# SensorStation_Board_v0_6.net
KiCad netlist of a schematic drawn in EAGLE
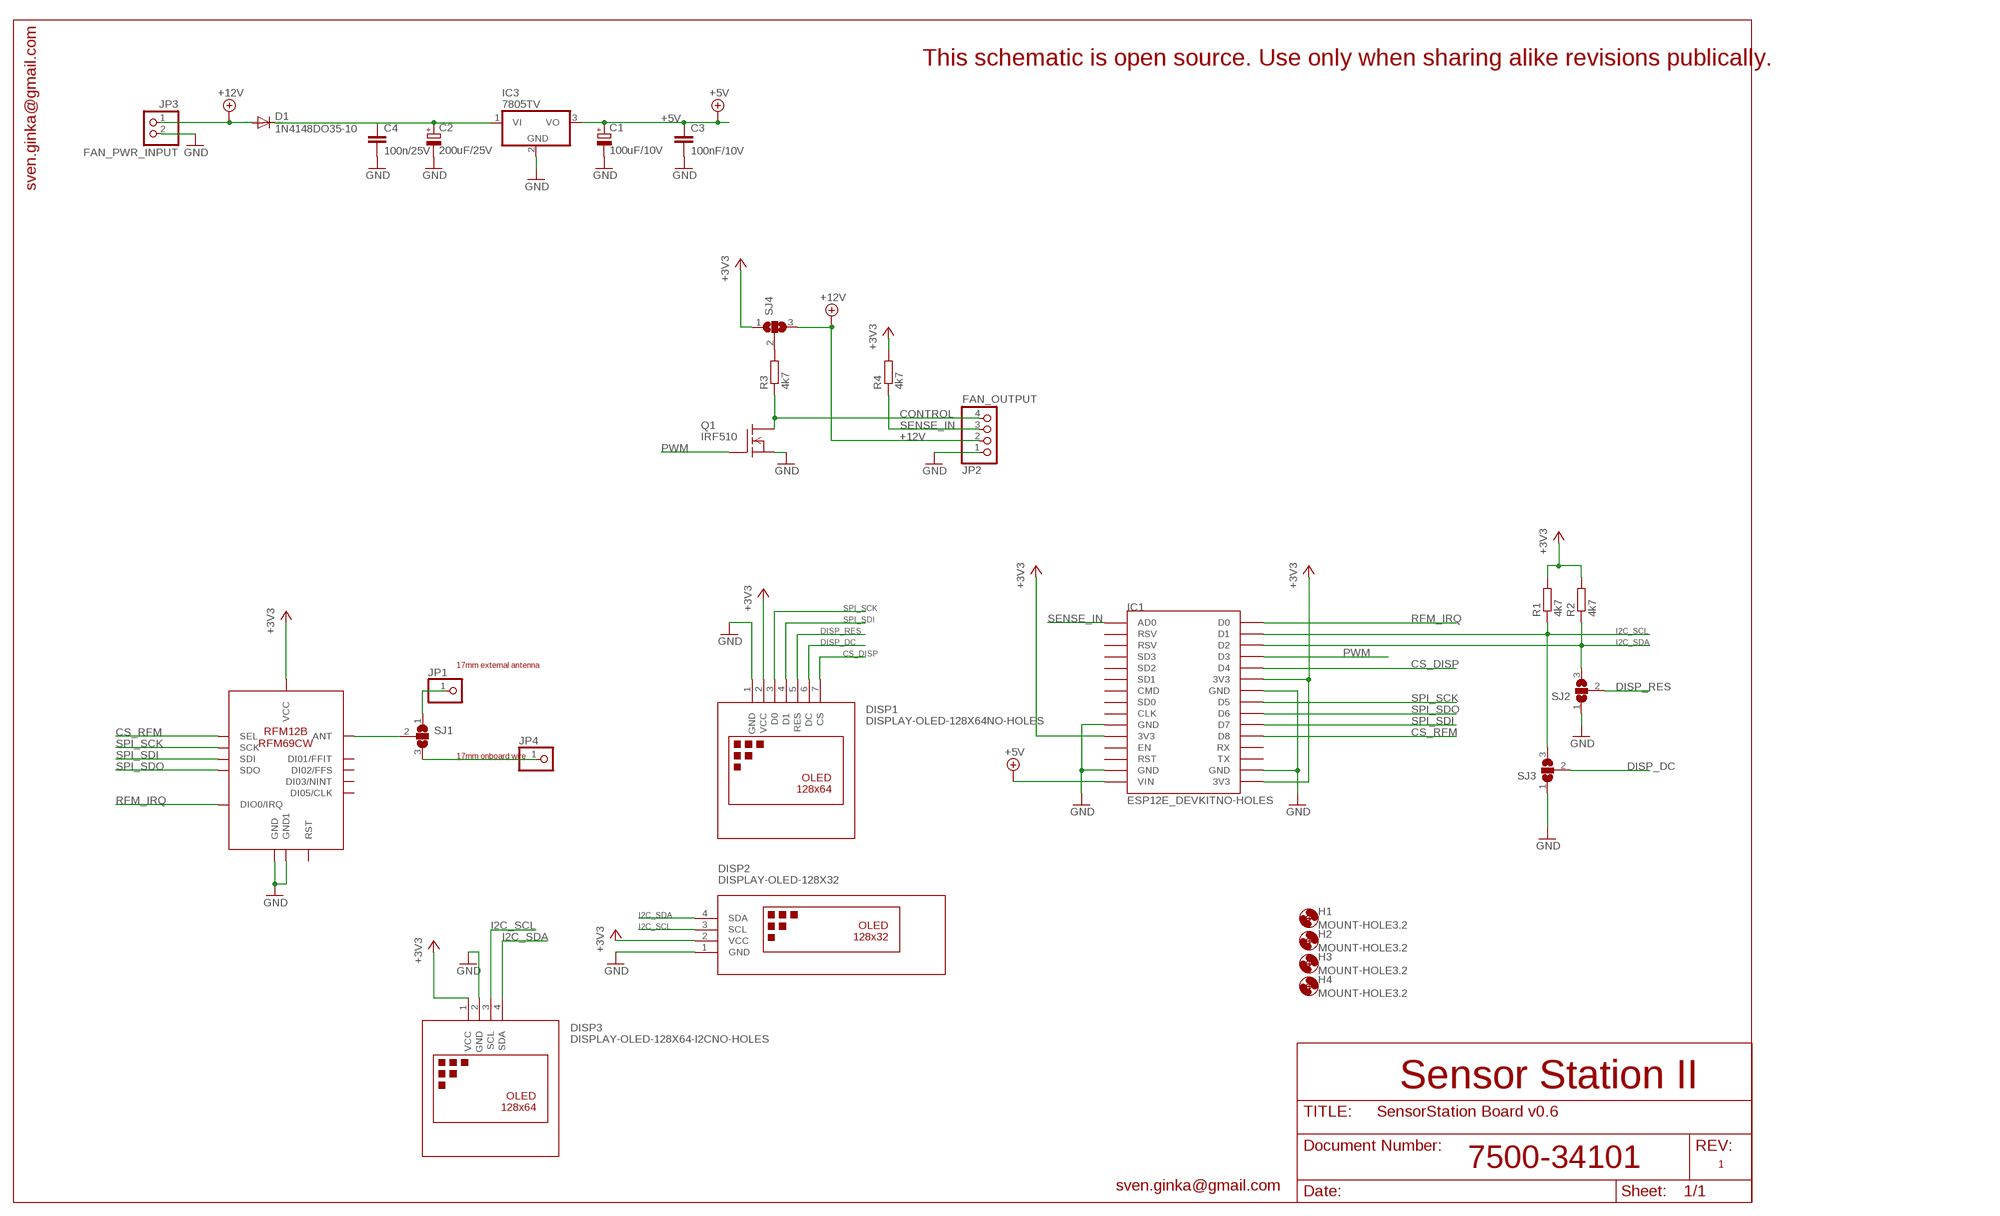
[diagram p0: schematic, sheet 1]

(export (version "E")
  (design (tool "Eeschema 10.0.6"))
  (components
    (comp (ref "C1")
      (value "100uF/10V")
      (footprint "eagle-import:E2,5-6")
      (libsource (lib "eagle-import") (part "CPOL-EUE2.5-6"))
    )
    (comp (ref "C2")
      (value "200uF/25V")
      (footprint "eagle-import:E2,5-6")
      (libsource (lib "eagle-import") (part "CPOL-EUE2.5-6"))
    )
    (comp (ref "C3")
      (value "100nF/10V")
      (footprint "eagle-import:C025-025X050")
      (libsource (lib "eagle-import") (part "C-EU025-025X050"))
    )
    (comp (ref "C4")
      (value "100n/25V")
      (footprint "eagle-import:C025-025X050")
      (libsource (lib "eagle-import") (part "C-EU025-025X050"))
    )
    (comp (ref "D1")
      (value "1N4148DO35-10")
      (footprint "eagle-import:DO35-10")
      (libsource (lib "eagle-import") (part "1N4148DO35-10"))
    )
    (comp (ref "DISP1")
      (value "DISPLAY-OLED-128X64NO-HOLES")
      (footprint "eagle-import:DISPLAY-OLED-128X64-NO-HOLES")
      (libsource (lib "eagle-import") (part "DISPLAY-OLED-128X64NO-HOLES"))
    )
    (comp (ref "DISP2")
      (value "DISPLAY-OLED-128X32")
      (footprint "eagle-import:DISPLAY-OLED-128X32")
      (libsource (lib "eagle-import") (part "DISPLAY-OLED-128X32"))
    )
    (comp (ref "DISP3")
      (value "DISPLAY-OLED-128X64-I2CNO-HOLES")
      (footprint "eagle-import:DISPLAY-OLED-128X64-I2C-NO-HOLES")
      (libsource (lib "eagle-import") (part "DISPLAY-OLED-128X64-I2CNO-HOLES"))
    )
    (comp (ref "H1")
      (value "MOUNT-HOLE3.2")
      (footprint "eagle-import:3,2")
      (libsource (lib "eagle-import") (part "MOUNT-HOLE3.2"))
    )
    (comp (ref "H2")
      (value "MOUNT-HOLE3.2")
      (footprint "eagle-import:3,2")
      (libsource (lib "eagle-import") (part "MOUNT-HOLE3.2"))
    )
    (comp (ref "H3")
      (value "MOUNT-HOLE3.2")
      (footprint "eagle-import:3,2")
      (libsource (lib "eagle-import") (part "MOUNT-HOLE3.2"))
    )
    (comp (ref "H4")
      (value "MOUNT-HOLE3.2")
      (footprint "eagle-import:3,2")
      (libsource (lib "eagle-import") (part "MOUNT-HOLE3.2"))
    )
    (comp (ref "IC1")
      (value "ESP12E_DEVKITNO-HOLES")
      (footprint "eagle-import:ESP12E_DEVKIT-NO-HOLES")
      (libsource (lib "eagle-import") (part "ESP12E_DEVKITNO-HOLES"))
    )
    (comp (ref "IC2")
      (value "RFM12B/69CW")
      (footprint "eagle-import:RFM12B_69CW")
      (libsource (lib "eagle-import") (part "RFM12B/69CW"))
    )
    (comp (ref "IC3")
      (value "7805TV")
      (footprint "eagle-import:TO220V")
      (libsource (lib "eagle-import") (part "78TV05"))
    )
    (comp (ref "JP1")
      (value "PINHD-1X1")
      (footprint "eagle-import:1X01")
      (libsource (lib "eagle-import") (part "PINHD-1X1"))
    )
    (comp (ref "JP2")
      (value "FAN_OUTPUT")
      (footprint "eagle-import:1X04")
      (libsource (lib "eagle-import") (part "PINHD-1X4"))
    )
    (comp (ref "JP3")
      (value "FAN_PWR_INPUT")
      (footprint "eagle-import:1X02")
      (libsource (lib "eagle-import") (part "PINHD-1X2"))
    )
    (comp (ref "JP4")
      (value "PINHD-1X1")
      (footprint "eagle-import:1X01")
      (libsource (lib "eagle-import") (part "PINHD-1X1"))
    )
    (comp (ref "Q1")
      (value "IRF510")
      (footprint "eagle-import:TO220")
      (libsource (lib "eagle-import") (part "IRF510"))
    )
    (comp (ref "R1")
      (value "4k7")
      (footprint "eagle-import:0204_5")
      (libsource (lib "eagle-import") (part "R-EU_0204/5"))
    )
    (comp (ref "R2")
      (value "4k7")
      (footprint "eagle-import:0204_5")
      (libsource (lib "eagle-import") (part "R-EU_0204/5"))
    )
    (comp (ref "R3")
      (value "4k7")
      (footprint "eagle-import:0204_5")
      (libsource (lib "eagle-import") (part "R-EU_0204/5"))
    )
    (comp (ref "R4")
      (value "4k7")
      (footprint "eagle-import:0204_5")
      (libsource (lib "eagle-import") (part "R-EU_0204/5"))
    )
    (comp (ref "SJ1")
      (value "SJ2W")
      (footprint "eagle-import:SJ_2")
      (libsource (lib "eagle-import") (part "SJ2W"))
    )
    (comp (ref "SJ2")
      (value "SJ2W")
      (footprint "eagle-import:SJ_2")
      (libsource (lib "eagle-import") (part "SJ2W"))
    )
    (comp (ref "SJ3")
      (value "SJ2W")
      (footprint "eagle-import:SJ_2")
      (libsource (lib "eagle-import") (part "SJ2W"))
    )
    (comp (ref "SJ4")
      (value "SJ2W")
      (footprint "eagle-import:SJ_2")
      (libsource (lib "eagle-import") (part "SJ2W"))
    )
  )
  (nets
    (net (code "1") (name "+3V3") (class "Default")
      (node (ref "DISP1") (pin "2") (pinfunction "VCC_2") (pintype "power_in"))
      (node (ref "DISP2") (pin "2") (pinfunction "VCC_2") (pintype "power_in"))
      (node (ref "DISP3") (pin "1") (pinfunction "VCC_1") (pintype "power_in"))
      (node (ref "IC1") (pin "3V3@0") (pinfunction "3V3_3V3@0") (pintype "bidirectional"))
      (node (ref "IC1") (pin "3V3@1") (pinfunction "3V3_3V3@1") (pintype "bidirectional"))
      (node (ref "IC1") (pin "3V3@2") (pinfunction "3V3_3V3@2") (pintype "bidirectional"))
      (node (ref "IC2") (pin "VDD") (pinfunction "VCC_VDD") (pintype "power_in"))
      (node (ref "R1") (pin "2") (pinfunction "2_2") (pintype "passive"))
      (node (ref "R2") (pin "2") (pinfunction "2_2") (pintype "passive"))
      (node (ref "R4") (pin "2") (pinfunction "2_2") (pintype "passive"))
      (node (ref "SJ4") (pin "1") (pinfunction "1_1") (pintype "passive"))
    )
    (net (code "2") (name "+5V") (class "Default")
      (node (ref "C1") (pin "+") (pinfunction "+_+") (pintype "passive"))
      (node (ref "C3") (pin "1") (pinfunction "1_1") (pintype "passive"))
      (node (ref "IC1") (pin "VIN") (pinfunction "VIN_VIN") (pintype "bidirectional"))
      (node (ref "IC3") (pin "3") (pinfunction "VO_3") (pintype "passive"))
    )
    (net (code "3") (name "+12V") (class "Default")
      (node (ref "D1") (pin "A") (pinfunction "A_A") (pintype "passive"))
      (node (ref "JP2") (pin "2") (pinfunction "2_2") (pintype "passive"))
      (node (ref "JP3") (pin "1") (pinfunction "1_1") (pintype "passive"))
      (node (ref "SJ4") (pin "3") (pinfunction "3_3") (pintype "passive"))
    )
    (net (code "4") (name "/CONTROL") (class "Default")
      (node (ref "JP2") (pin "4") (pinfunction "4_4") (pintype "passive"))
      (node (ref "Q1") (pin "2") (pinfunction "D_2") (pintype "passive"))
      (node (ref "R3") (pin "1") (pinfunction "1_1") (pintype "passive"))
    )
    (net (code "5") (name "/CS_DISP") (class "Default")
      (node (ref "DISP1") (pin "7") (pinfunction "CS_7") (pintype "bidirectional"))
      (node (ref "IC1") (pin "D4") (pinfunction "D4_D4") (pintype "bidirectional"))
    )
    (net (code "6") (name "/CS_RFM") (class "Default")
      (node (ref "IC1") (pin "D8") (pinfunction "D8_D8") (pintype "bidirectional"))
      (node (ref "IC2") (pin "SEL") (pinfunction "SEL_SEL") (pintype "input"))
    )
    (net (code "7") (name "/DISP_DC") (class "Default")
      (node (ref "DISP1") (pin "6") (pinfunction "DC_6") (pintype "bidirectional"))
      (node (ref "SJ3") (pin "2") (pinfunction "2_2") (pintype "passive"))
    )
    (net (code "8") (name "/DISP_RES") (class "Default")
      (node (ref "DISP1") (pin "5") (pinfunction "RES_5") (pintype "bidirectional"))
      (node (ref "SJ2") (pin "2") (pinfunction "2_2") (pintype "passive"))
    )
    (net (code "9") (name "/I2C_SCL") (class "Default")
      (node (ref "DISP2") (pin "3") (pinfunction "SCL_3") (pintype "bidirectional"))
      (node (ref "DISP3") (pin "3") (pinfunction "SCL_3") (pintype "bidirectional"))
      (node (ref "IC1") (pin "D1") (pinfunction "D1_D1") (pintype "bidirectional"))
      (node (ref "R1") (pin "1") (pinfunction "1_1") (pintype "passive"))
      (node (ref "SJ3") (pin "3") (pinfunction "3_3") (pintype "passive"))
    )
    (net (code "10") (name "/I2C_SDA") (class "Default")
      (node (ref "DISP2") (pin "4") (pinfunction "SDA_4") (pintype "bidirectional"))
      (node (ref "DISP3") (pin "4") (pinfunction "SDA_4") (pintype "bidirectional"))
      (node (ref "IC1") (pin "D2") (pinfunction "D2_D2") (pintype "bidirectional"))
      (node (ref "R2") (pin "1") (pinfunction "1_1") (pintype "passive"))
      (node (ref "SJ2") (pin "3") (pinfunction "3_3") (pintype "passive"))
    )
    (net (code "11") (name "/PWM") (class "Default")
      (node (ref "IC1") (pin "D3") (pinfunction "D3_D3") (pintype "bidirectional"))
      (node (ref "Q1") (pin "1") (pinfunction "G_1") (pintype "passive"))
    )
    (net (code "12") (name "/RFM_IRQ") (class "Default")
      (node (ref "IC1") (pin "D0") (pinfunction "D0_D0") (pintype "bidirectional"))
      (node (ref "IC2") (pin "IRQ") (pinfunction "DIO0/IRQ_IRQ") (pintype "open_collector"))
    )
    (net (code "13") (name "/SENSE_IN") (class "Default")
      (node (ref "IC1") (pin "AD0") (pinfunction "AD0_AD0") (pintype "bidirectional"))
      (node (ref "JP2") (pin "3") (pinfunction "3_3") (pintype "passive"))
      (node (ref "R4") (pin "1") (pinfunction "1_1") (pintype "passive"))
    )
    (net (code "14") (name "/SPI_SCK") (class "Default")
      (node (ref "DISP1") (pin "3") (pinfunction "D0_3") (pintype "bidirectional"))
      (node (ref "IC1") (pin "D5") (pinfunction "D5_D5") (pintype "bidirectional"))
      (node (ref "IC2") (pin "SCK") (pinfunction "SCK_SCK") (pintype "input"))
    )
    (net (code "15") (name "/SPI_SDI") (class "Default")
      (node (ref "DISP1") (pin "4") (pinfunction "D1_4") (pintype "bidirectional"))
      (node (ref "IC1") (pin "D7") (pinfunction "D7_D7") (pintype "bidirectional"))
      (node (ref "IC2") (pin "SDI") (pinfunction "SDI_SDI") (pintype "input"))
    )
    (net (code "16") (name "/SPI_SDO") (class "Default")
      (node (ref "IC1") (pin "D6") (pinfunction "D6_D6") (pintype "bidirectional"))
      (node (ref "IC2") (pin "SDO") (pinfunction "SDO_SDO") (pintype "output"))
    )
    (net (code "17") (name "GND") (class "Default")
      (node (ref "C1") (pin "-") (pinfunction "-_-") (pintype "passive"))
      (node (ref "C2") (pin "-") (pinfunction "-_-") (pintype "passive"))
      (node (ref "C3") (pin "2") (pinfunction "2_2") (pintype "passive"))
      (node (ref "C4") (pin "2") (pinfunction "2_2") (pintype "passive"))
      (node (ref "DISP1") (pin "1") (pinfunction "GND_1") (pintype "power_in"))
      (node (ref "DISP2") (pin "1") (pinfunction "GND_1") (pintype "power_in"))
      (node (ref "DISP3") (pin "2") (pinfunction "GND_2") (pintype "power_in"))
      (node (ref "IC1") (pin "GND@0") (pinfunction "GND_GND@0") (pintype "bidirectional"))
      (node (ref "IC1") (pin "GND@1") (pinfunction "GND_GND@1") (pintype "bidirectional"))
      (node (ref "IC1") (pin "GND@2") (pinfunction "GND_GND@2") (pintype "bidirectional"))
      (node (ref "IC1") (pin "GND@3") (pinfunction "GND_GND@3") (pintype "bidirectional"))
      (node (ref "IC2") (pin "GND") (pinfunction "GND_GND") (pintype "power_in"))
      (node (ref "IC2") (pin "GND1") (pinfunction "GND1_GND1") (pintype "power_in"))
      (node (ref "IC3") (pin "2") (pinfunction "GND_2") (pintype "passive"))
      (node (ref "JP2") (pin "1") (pinfunction "1_1") (pintype "passive"))
      (node (ref "JP3") (pin "2") (pinfunction "2_2") (pintype "passive"))
      (node (ref "Q1") (pin "3") (pinfunction "S_3") (pintype "passive"))
      (node (ref "SJ2") (pin "1") (pinfunction "1_1") (pintype "passive"))
      (node (ref "SJ3") (pin "1") (pinfunction "1_1") (pintype "passive"))
    )
    (net (code "18") (name "Net-(IC2-PadANT)") (class "Default")
      (node (ref "IC2") (pin "ANT") (pinfunction "ANT_ANT") (pintype "passive"))
      (node (ref "SJ1") (pin "2") (pinfunction "2_2") (pintype "passive"))
    )
    (net (code "19") (name "Net-(IC3-VI)") (class "Default")
      (node (ref "C2") (pin "+") (pinfunction "+_+") (pintype "passive"))
      (node (ref "C4") (pin "1") (pinfunction "1_1") (pintype "passive"))
      (node (ref "D1") (pin "C") (pinfunction "C_C") (pintype "passive"))
      (node (ref "IC3") (pin "1") (pinfunction "VI_1") (pintype "input"))
    )
    (net (code "20") (name "Net-(JP1-Pad1)") (class "Default")
      (node (ref "JP1") (pin "1") (pinfunction "1_1") (pintype "passive"))
      (node (ref "SJ1") (pin "1") (pinfunction "1_1") (pintype "passive"))
    )
    (net (code "21") (name "Net-(JP4-Pad1)") (class "Default")
      (node (ref "JP4") (pin "1") (pinfunction "1_1") (pintype "passive"))
      (node (ref "SJ1") (pin "3") (pinfunction "3_3") (pintype "passive"))
    )
    (net (code "22") (name "Net-(R3-Pad2)") (class "Default")
      (node (ref "R3") (pin "2") (pinfunction "2_2") (pintype "passive"))
      (node (ref "SJ4") (pin "2") (pinfunction "2_2") (pintype "passive"))
    )
    (net (code "23") (name "unconnected-(IC1-PadCLK)") (class "Default")
      (node (ref "IC1") (pin "CLK") (pinfunction "CLK_CLK") (pintype "bidirectional"))
    )
    (net (code "24") (name "unconnected-(IC1-PadCMD)") (class "Default")
      (node (ref "IC1") (pin "CMD") (pinfunction "CMD_CMD") (pintype "bidirectional"))
    )
    (net (code "25") (name "unconnected-(IC1-PadEN)") (class "Default")
      (node (ref "IC1") (pin "EN") (pinfunction "EN_EN") (pintype "bidirectional"))
    )
    (net (code "26") (name "unconnected-(IC1-PadRST)") (class "Default")
      (node (ref "IC1") (pin "RST") (pinfunction "RST_RST") (pintype "bidirectional"))
    )
    (net (code "27") (name "unconnected-(IC1-PadRX)") (class "Default")
      (node (ref "IC1") (pin "RX") (pinfunction "RX_RX") (pintype "bidirectional"))
    )
    (net (code "28") (name "unconnected-(IC1-PadSD0)") (class "Default")
      (node (ref "IC1") (pin "SD0") (pinfunction "SD0_SD0") (pintype "bidirectional"))
    )
    (net (code "29") (name "unconnected-(IC1-PadSD1)") (class "Default")
      (node (ref "IC1") (pin "SD1") (pinfunction "SD1_SD1") (pintype "bidirectional"))
    )
    (net (code "30") (name "unconnected-(IC1-PadSD2)") (class "Default")
      (node (ref "IC1") (pin "SD2") (pinfunction "SD2_SD2") (pintype "bidirectional"))
    )
    (net (code "31") (name "unconnected-(IC1-PadSD3)") (class "Default")
      (node (ref "IC1") (pin "SD3") (pinfunction "SD3_SD3") (pintype "bidirectional"))
    )
    (net (code "32") (name "unconnected-(IC1-PadTX)") (class "Default")
      (node (ref "IC1") (pin "TX") (pinfunction "TX_TX") (pintype "bidirectional"))
    )
    (net (code "33") (name "unconnected-(IC1-RSV-PadRSV@0)") (class "Default")
      (node (ref "IC1") (pin "RSV@0") (pinfunction "RSV_RSV@0") (pintype "bidirectional"))
    )
    (net (code "34") (name "unconnected-(IC1-RSV-PadRSV@1)") (class "Default")
      (node (ref "IC1") (pin "RSV@1") (pinfunction "RSV_RSV@1") (pintype "bidirectional"))
    )
    (net (code "35") (name "unconnected-(IC2-DI01{slash}FFIT-PadFFIT)") (class "Default")
      (node (ref "IC2") (pin "FFIT") (pinfunction "DI01/FFIT_FFIT") (pintype "passive"))
    )
    (net (code "36") (name "unconnected-(IC2-DI02{slash}FFS-PadFFS)") (class "Default")
      (node (ref "IC2") (pin "FFS") (pinfunction "DI02/FFS_FFS") (pintype "bidirectional"))
    )
    (net (code "37") (name "unconnected-(IC2-DI03{slash}NINT-PadNINT)") (class "Default")
      (node (ref "IC2") (pin "NINT") (pinfunction "DI03/NINT_NINT") (pintype "passive"))
    )
    (net (code "38") (name "unconnected-(IC2-DI05{slash}CLK-PadCLK)") (class "Default")
      (node (ref "IC2") (pin "CLK") (pinfunction "DI05/CLK_CLK") (pintype "passive"))
    )
    (net (code "39") (name "unconnected-(IC2-PadRST)") (class "Default")
      (node (ref "IC2") (pin "RST") (pinfunction "RST_RST") (pintype "open_collector"))
    )
  )
)
